# SCH_Optical_Endstops_2025-04-08.net
KiCad netlist of a schematic drawn in EasyEDA
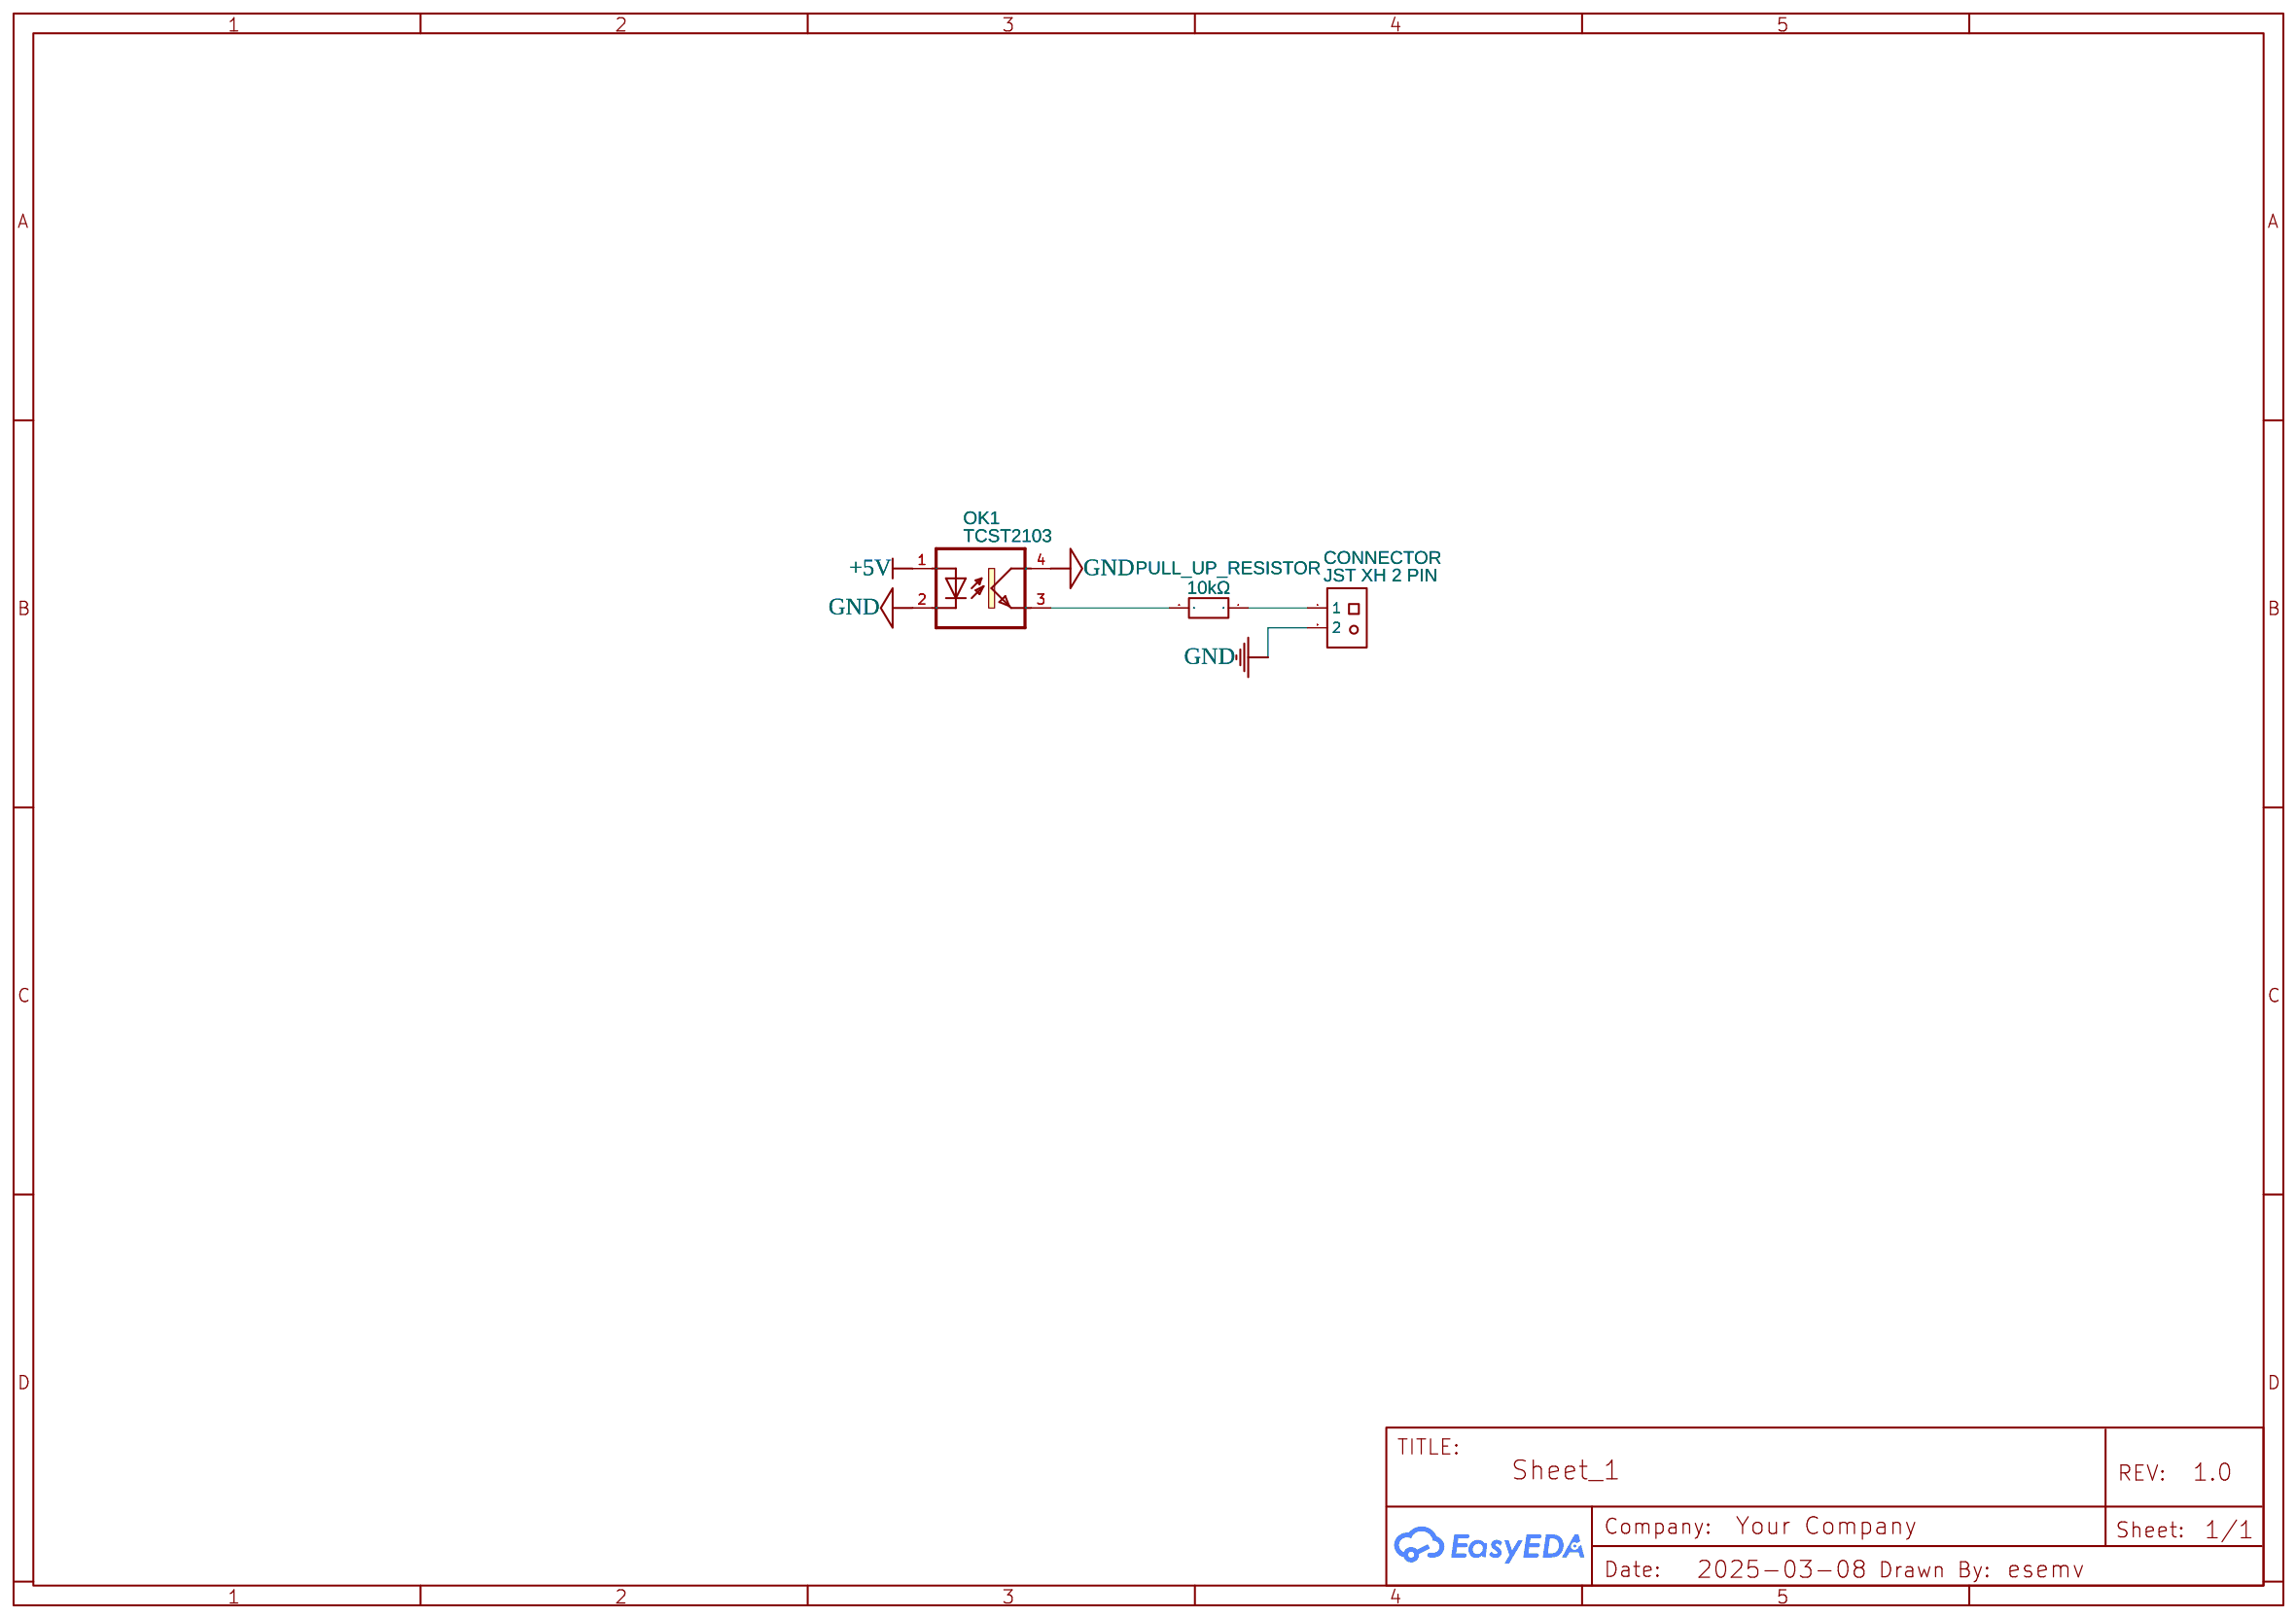
[diagram p0: schematic sheet]

(export (version "E")
  (design (tool "Eeschema 10.0.6"))
  (components
    (comp (ref "CONNECTOR")
      (value "JST XH 2 PIN")
      (fields (field (name "Manufacturer Part") "JST_XH CONNECTOR"))
      (libsource (lib "") (part "JST XH 2 PIN"))
    )
    (comp (ref "OK1")
      (value "TCST2103")
      (fields (field (name "Manufacturer") "VISHAY"))
      (libsource (lib "") (part "TCST2103"))
    )
    (comp (ref "PULL_UP_RESISTOR")
      (value "10kΩ")
      (fields (field (name "Manufacturer Part") "MMFR6518B10K0V9") (field (name "Manufacturer") "RESI(开步睿思)"))
      (libsource (lib "") (part "MMFR6518B10K0V9"))
    )
  )
  (nets
    (net (code "1") (name "+5V") (class "Default")
      (node (ref "OK1") (pin "1") (pinfunction "A_1") (pintype "bidirectional"))
    )
    (net (code "2") (name "GND") (class "Default")
      (node (ref "CONNECTOR") (pin "2") (pinfunction "2_2") (pintype "unspecified"))
      (node (ref "OK1") (pin "2") (pinfunction "C_2") (pintype "bidirectional"))
      (node (ref "OK1") (pin "4") (pinfunction "COL_4") (pintype "bidirectional"))
    )
    (net (code "3") (name "Net-(CONNECTOR-Pad1)") (class "Default")
      (node (ref "CONNECTOR") (pin "1") (pinfunction "1_1") (pintype "unspecified"))
      (node (ref "PULL_UP_RESISTOR") (pin "1") (pinfunction "1_1") (pintype "unspecified"))
    )
    (net (code "4") (name "Net-(OK1-EMIT)") (class "Default")
      (node (ref "OK1") (pin "3") (pinfunction "EMIT_3") (pintype "bidirectional"))
      (node (ref "PULL_UP_RESISTOR") (pin "2") (pinfunction "2_2") (pintype "unspecified"))
    )
  )
)
